# try_two.net
KiCad netlist of a schematic drawn in EAGLE
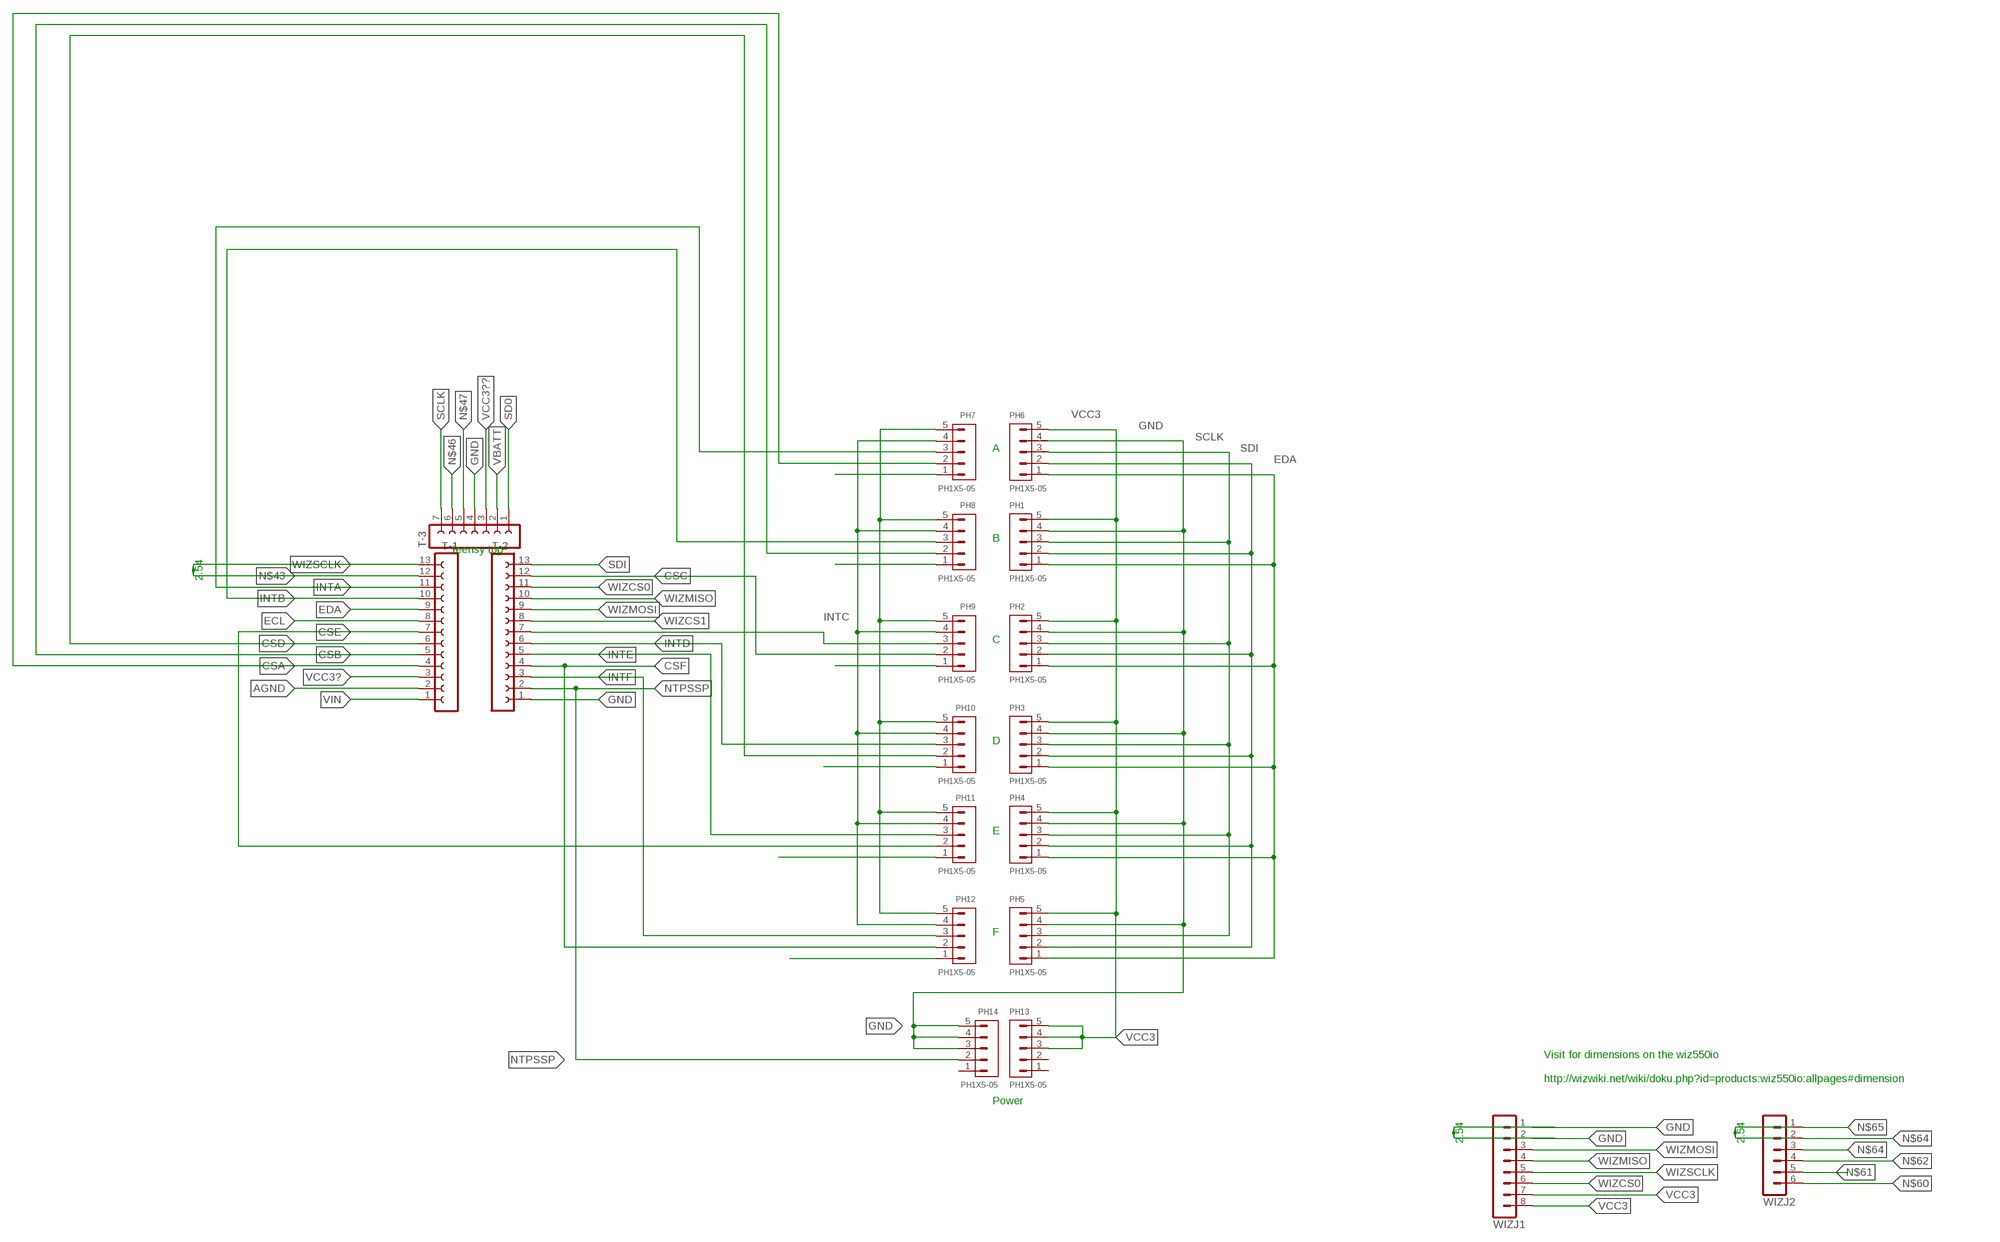
[diagram p0: schematic, sheet 1]

(export (version "E")
  (design (tool "Eeschema 10.0.6"))
  (components
    (comp (ref "PH1")
      (value "PH1X5-05")
      (footprint "eagle-import:PH005-1-5")
      (libsource (lib "eagle-import") (part "PH1X5-05"))
    )
    (comp (ref "PH2")
      (value "PH1X5-05")
      (footprint "eagle-import:PH005-1-5")
      (libsource (lib "eagle-import") (part "PH1X5-05"))
    )
    (comp (ref "PH3")
      (value "PH1X5-05")
      (footprint "eagle-import:PH005-1-5")
      (libsource (lib "eagle-import") (part "PH1X5-05"))
    )
    (comp (ref "PH4")
      (value "PH1X5-05")
      (footprint "eagle-import:PH005-1-5")
      (libsource (lib "eagle-import") (part "PH1X5-05"))
    )
    (comp (ref "PH5")
      (value "PH1X5-05")
      (footprint "eagle-import:PH005-1-5")
      (libsource (lib "eagle-import") (part "PH1X5-05"))
    )
    (comp (ref "PH6")
      (value "PH1X5-05")
      (footprint "eagle-import:PH005-1-5")
      (libsource (lib "eagle-import") (part "PH1X5-05"))
    )
    (comp (ref "PH7")
      (value "PH1X5-05")
      (footprint "eagle-import:PH005-1-5")
      (libsource (lib "eagle-import") (part "PH1X5-05"))
    )
    (comp (ref "PH8")
      (value "PH1X5-05")
      (footprint "eagle-import:PH005-1-5")
      (libsource (lib "eagle-import") (part "PH1X5-05"))
    )
    (comp (ref "PH9")
      (value "PH1X5-05")
      (footprint "eagle-import:PH005-1-5")
      (libsource (lib "eagle-import") (part "PH1X5-05"))
    )
    (comp (ref "PH10")
      (value "PH1X5-05")
      (footprint "eagle-import:PH005-1-5")
      (libsource (lib "eagle-import") (part "PH1X5-05"))
    )
    (comp (ref "PH11")
      (value "PH1X5-05")
      (footprint "eagle-import:PH005-1-5")
      (libsource (lib "eagle-import") (part "PH1X5-05"))
    )
    (comp (ref "PH12")
      (value "PH1X5-05")
      (footprint "eagle-import:PH005-1-5")
      (libsource (lib "eagle-import") (part "PH1X5-05"))
    )
    (comp (ref "PH13")
      (value "PH1X5-05")
      (footprint "eagle-import:PH005-1-5")
      (libsource (lib "eagle-import") (part "PH1X5-05"))
    )
    (comp (ref "PH14")
      (value "PH1X5-05")
      (footprint "eagle-import:PH005-1-5")
      (libsource (lib "eagle-import") (part "PH1X5-05"))
    )
    (comp (ref "T-1")
      (value "FE13-1")
      (footprint "eagle-import:FE13")
      (libsource (lib "eagle-import") (part "FE13-1"))
    )
    (comp (ref "T-2")
      (value "FE13-1")
      (footprint "eagle-import:FE13")
      (libsource (lib "eagle-import") (part "FE13-1"))
    )
    (comp (ref "T-3")
      (value "FE07-1")
      (footprint "eagle-import:FE07")
      (libsource (lib "eagle-import") (part "FE07-1"))
    )
    (comp (ref "WIZJ1")
      (value "MA08-1")
      (footprint "eagle-import:MA08-1")
      (libsource (lib "eagle-import") (part "MA08-1"))
    )
    (comp (ref "WIZJ2")
      (value "MA06-1")
      (footprint "eagle-import:MA06-1")
      (libsource (lib "eagle-import") (part "MA06-1"))
    )
  )
  (nets
    (net (code "1") (name "/INTC") (class "Default")
      (node (ref "PH9") (pin "3") (pinfunction "3_3") (pintype "bidirectional"))
      (node (ref "T-2") (pin "7") (pinfunction "7_7") (pintype "passive"))
    )
    (net (code "2") (name "AGND") (class "Default")
      (node (ref "T-1") (pin "2") (pinfunction "2_2") (pintype "passive"))
    )
    (net (code "3") (name "CSA") (class "Default")
      (node (ref "PH7") (pin "2") (pinfunction "2_2") (pintype "bidirectional"))
      (node (ref "T-1") (pin "4") (pinfunction "4_4") (pintype "passive"))
    )
    (net (code "4") (name "CSB") (class "Default")
      (node (ref "PH8") (pin "2") (pinfunction "2_2") (pintype "bidirectional"))
      (node (ref "T-1") (pin "5") (pinfunction "5_5") (pintype "passive"))
    )
    (net (code "5") (name "CSC") (class "Default")
      (node (ref "PH9") (pin "2") (pinfunction "2_2") (pintype "bidirectional"))
      (node (ref "T-2") (pin "12") (pinfunction "12_12") (pintype "passive"))
    )
    (net (code "6") (name "CSD") (class "Default")
      (node (ref "PH10") (pin "2") (pinfunction "2_2") (pintype "bidirectional"))
      (node (ref "T-1") (pin "6") (pinfunction "6_6") (pintype "passive"))
    )
    (net (code "7") (name "CSE") (class "Default")
      (node (ref "PH11") (pin "2") (pinfunction "2_2") (pintype "bidirectional"))
      (node (ref "T-1") (pin "7") (pinfunction "7_7") (pintype "passive"))
    )
    (net (code "8") (name "CSF") (class "Default")
      (node (ref "PH12") (pin "2") (pinfunction "2_2") (pintype "bidirectional"))
      (node (ref "T-2") (pin "4") (pinfunction "4_4") (pintype "passive"))
    )
    (net (code "9") (name "ECL") (class "Default")
      (node (ref "PH10") (pin "5") (pinfunction "5_5") (pintype "bidirectional"))
      (node (ref "PH11") (pin "5") (pinfunction "5_5") (pintype "bidirectional"))
      (node (ref "PH12") (pin "5") (pinfunction "5_5") (pintype "bidirectional"))
      (node (ref "PH7") (pin "5") (pinfunction "5_5") (pintype "bidirectional"))
      (node (ref "PH8") (pin "5") (pinfunction "5_5") (pintype "bidirectional"))
      (node (ref "PH9") (pin "5") (pinfunction "5_5") (pintype "bidirectional"))
      (node (ref "T-1") (pin "8") (pinfunction "8_8") (pintype "passive"))
    )
    (net (code "10") (name "EDA") (class "Default")
      (node (ref "PH1") (pin "1") (pinfunction "1_1") (pintype "bidirectional"))
      (node (ref "PH2") (pin "1") (pinfunction "1_1") (pintype "bidirectional"))
      (node (ref "PH3") (pin "1") (pinfunction "1_1") (pintype "bidirectional"))
      (node (ref "PH4") (pin "1") (pinfunction "1_1") (pintype "bidirectional"))
      (node (ref "PH5") (pin "1") (pinfunction "1_1") (pintype "bidirectional"))
      (node (ref "PH6") (pin "1") (pinfunction "1_1") (pintype "bidirectional"))
      (node (ref "T-1") (pin "9") (pinfunction "9_9") (pintype "passive"))
    )
    (net (code "11") (name "GND") (class "Default")
      (node (ref "PH1") (pin "4") (pinfunction "4_4") (pintype "bidirectional"))
      (node (ref "PH14") (pin "3") (pinfunction "3_3") (pintype "bidirectional"))
      (node (ref "PH14") (pin "4") (pinfunction "4_4") (pintype "bidirectional"))
      (node (ref "PH14") (pin "5") (pinfunction "5_5") (pintype "bidirectional"))
      (node (ref "PH2") (pin "4") (pinfunction "4_4") (pintype "bidirectional"))
      (node (ref "PH3") (pin "4") (pinfunction "4_4") (pintype "bidirectional"))
      (node (ref "PH4") (pin "4") (pinfunction "4_4") (pintype "bidirectional"))
      (node (ref "PH5") (pin "4") (pinfunction "4_4") (pintype "bidirectional"))
      (node (ref "PH6") (pin "4") (pinfunction "4_4") (pintype "bidirectional"))
      (node (ref "T-2") (pin "1") (pinfunction "1_1") (pintype "passive"))
      (node (ref "T-3") (pin "4") (pinfunction "4_4") (pintype "passive"))
      (node (ref "WIZJ1") (pin "1") (pinfunction "1_1") (pintype "passive"))
      (node (ref "WIZJ1") (pin "2") (pinfunction "2_2") (pintype "passive"))
    )
    (net (code "12") (name "INTA") (class "Default")
      (node (ref "PH7") (pin "3") (pinfunction "3_3") (pintype "bidirectional"))
      (node (ref "T-1") (pin "11") (pinfunction "11_11") (pintype "passive"))
    )
    (net (code "13") (name "INTB") (class "Default")
      (node (ref "PH8") (pin "3") (pinfunction "3_3") (pintype "bidirectional"))
      (node (ref "T-1") (pin "10") (pinfunction "10_10") (pintype "passive"))
    )
    (net (code "14") (name "INTD") (class "Default")
      (node (ref "PH10") (pin "3") (pinfunction "3_3") (pintype "bidirectional"))
      (node (ref "T-2") (pin "6") (pinfunction "6_6") (pintype "passive"))
    )
    (net (code "15") (name "INTE") (class "Default")
      (node (ref "PH11") (pin "3") (pinfunction "3_3") (pintype "bidirectional"))
      (node (ref "T-2") (pin "5") (pinfunction "5_5") (pintype "passive"))
    )
    (net (code "16") (name "INTF") (class "Default")
      (node (ref "PH12") (pin "3") (pinfunction "3_3") (pintype "bidirectional"))
      (node (ref "T-2") (pin "3") (pinfunction "3_3") (pintype "passive"))
    )
    (net (code "17") (name "N$43") (class "Default")
      (node (ref "T-1") (pin "12") (pinfunction "12_12") (pintype "passive"))
    )
    (net (code "18") (name "N$46") (class "Default")
      (node (ref "T-3") (pin "6") (pinfunction "6_6") (pintype "passive"))
    )
    (net (code "19") (name "N$47") (class "Default")
      (node (ref "T-3") (pin "5") (pinfunction "5_5") (pintype "passive"))
    )
    (net (code "20") (name "N$60") (class "Default")
      (node (ref "WIZJ2") (pin "6") (pinfunction "6_6") (pintype "passive"))
    )
    (net (code "21") (name "N$61") (class "Default")
      (node (ref "WIZJ2") (pin "5") (pinfunction "5_5") (pintype "passive"))
    )
    (net (code "22") (name "N$62") (class "Default")
      (node (ref "WIZJ2") (pin "4") (pinfunction "4_4") (pintype "passive"))
    )
    (net (code "23") (name "N$64") (class "Default")
      (node (ref "WIZJ2") (pin "2") (pinfunction "2_2") (pintype "passive"))
    )
    (net (code "24") (name "N$65") (class "Default")
      (node (ref "WIZJ2") (pin "1") (pinfunction "1_1") (pintype "passive"))
    )
    (net (code "25") (name "NTPSSP") (class "Default")
      (node (ref "PH14") (pin "2") (pinfunction "2_2") (pintype "bidirectional"))
      (node (ref "T-2") (pin "2") (pinfunction "2_2") (pintype "passive"))
    )
    (net (code "26") (name "SCLK") (class "Default")
      (node (ref "PH1") (pin "3") (pinfunction "3_3") (pintype "bidirectional"))
      (node (ref "PH2") (pin "3") (pinfunction "3_3") (pintype "bidirectional"))
      (node (ref "PH3") (pin "3") (pinfunction "3_3") (pintype "bidirectional"))
      (node (ref "PH4") (pin "3") (pinfunction "3_3") (pintype "bidirectional"))
      (node (ref "PH5") (pin "3") (pinfunction "3_3") (pintype "bidirectional"))
      (node (ref "PH6") (pin "3") (pinfunction "3_3") (pintype "bidirectional"))
      (node (ref "T-3") (pin "7") (pinfunction "7_7") (pintype "passive"))
    )
    (net (code "27") (name "SD0") (class "Default")
      (node (ref "PH10") (pin "4") (pinfunction "4_4") (pintype "bidirectional"))
      (node (ref "PH11") (pin "4") (pinfunction "4_4") (pintype "bidirectional"))
      (node (ref "PH12") (pin "4") (pinfunction "4_4") (pintype "bidirectional"))
      (node (ref "PH7") (pin "4") (pinfunction "4_4") (pintype "bidirectional"))
      (node (ref "PH8") (pin "4") (pinfunction "4_4") (pintype "bidirectional"))
      (node (ref "PH9") (pin "4") (pinfunction "4_4") (pintype "bidirectional"))
      (node (ref "T-3") (pin "1") (pinfunction "1_1") (pintype "passive"))
    )
    (net (code "28") (name "SDI") (class "Default")
      (node (ref "PH1") (pin "2") (pinfunction "2_2") (pintype "bidirectional"))
      (node (ref "PH2") (pin "2") (pinfunction "2_2") (pintype "bidirectional"))
      (node (ref "PH3") (pin "2") (pinfunction "2_2") (pintype "bidirectional"))
      (node (ref "PH4") (pin "2") (pinfunction "2_2") (pintype "bidirectional"))
      (node (ref "PH5") (pin "2") (pinfunction "2_2") (pintype "bidirectional"))
      (node (ref "PH6") (pin "2") (pinfunction "2_2") (pintype "bidirectional"))
      (node (ref "T-2") (pin "13") (pinfunction "13_13") (pintype "passive"))
    )
    (net (code "29") (name "VBATT") (class "Default")
      (node (ref "T-3") (pin "2") (pinfunction "2_2") (pintype "passive"))
    )
    (net (code "30") (name "VCC3") (class "Default")
      (node (ref "PH1") (pin "5") (pinfunction "5_5") (pintype "bidirectional"))
      (node (ref "PH13") (pin "3") (pinfunction "3_3") (pintype "bidirectional"))
      (node (ref "PH13") (pin "4") (pinfunction "4_4") (pintype "bidirectional"))
      (node (ref "PH13") (pin "5") (pinfunction "5_5") (pintype "bidirectional"))
      (node (ref "PH2") (pin "5") (pinfunction "5_5") (pintype "bidirectional"))
      (node (ref "PH3") (pin "5") (pinfunction "5_5") (pintype "bidirectional"))
      (node (ref "PH4") (pin "5") (pinfunction "5_5") (pintype "bidirectional"))
      (node (ref "PH5") (pin "5") (pinfunction "5_5") (pintype "bidirectional"))
      (node (ref "PH6") (pin "5") (pinfunction "5_5") (pintype "bidirectional"))
      (node (ref "WIZJ1") (pin "7") (pinfunction "7_7") (pintype "passive"))
      (node (ref "WIZJ1") (pin "8") (pinfunction "8_8") (pintype "passive"))
    )
    (net (code "31") (name "VCC3?") (class "Default")
      (node (ref "T-1") (pin "3") (pinfunction "3_3") (pintype "passive"))
    )
    (net (code "32") (name "VCC3??") (class "Default")
      (node (ref "T-3") (pin "3") (pinfunction "3_3") (pintype "passive"))
    )
    (net (code "33") (name "VIN") (class "Default")
      (node (ref "T-1") (pin "1") (pinfunction "1_1") (pintype "passive"))
    )
    (net (code "34") (name "WIZCS0") (class "Default")
      (node (ref "T-2") (pin "11") (pinfunction "11_11") (pintype "passive"))
      (node (ref "WIZJ1") (pin "6") (pinfunction "6_6") (pintype "passive"))
    )
    (net (code "35") (name "WIZCS1") (class "Default")
      (node (ref "T-2") (pin "8") (pinfunction "8_8") (pintype "passive"))
    )
    (net (code "36") (name "WIZMISO") (class "Default")
      (node (ref "T-2") (pin "10") (pinfunction "10_10") (pintype "passive"))
      (node (ref "WIZJ1") (pin "4") (pinfunction "4_4") (pintype "passive"))
    )
    (net (code "37") (name "WIZMOSI") (class "Default")
      (node (ref "T-2") (pin "9") (pinfunction "9_9") (pintype "passive"))
      (node (ref "WIZJ1") (pin "3") (pinfunction "3_3") (pintype "passive"))
    )
    (net (code "38") (name "WIZSCLK") (class "Default")
      (node (ref "T-1") (pin "13") (pinfunction "13_13") (pintype "passive"))
      (node (ref "WIZJ1") (pin "5") (pinfunction "5_5") (pintype "passive"))
    )
    (net (code "39") (name "unconnected-(PH7-Pad1)") (class "Default")
      (node (ref "PH7") (pin "1") (pinfunction "1_1") (pintype "bidirectional"))
    )
    (net (code "40") (name "unconnected-(PH8-Pad1)") (class "Default")
      (node (ref "PH8") (pin "1") (pinfunction "1_1") (pintype "bidirectional"))
    )
    (net (code "41") (name "unconnected-(PH9-Pad1)") (class "Default")
      (node (ref "PH9") (pin "1") (pinfunction "1_1") (pintype "bidirectional"))
    )
    (net (code "42") (name "unconnected-(PH10-Pad1)") (class "Default")
      (node (ref "PH10") (pin "1") (pinfunction "1_1") (pintype "bidirectional"))
    )
    (net (code "43") (name "unconnected-(PH11-Pad1)") (class "Default")
      (node (ref "PH11") (pin "1") (pinfunction "1_1") (pintype "bidirectional"))
    )
    (net (code "44") (name "unconnected-(PH12-Pad1)") (class "Default")
      (node (ref "PH12") (pin "1") (pinfunction "1_1") (pintype "bidirectional"))
    )
    (net (code "45") (name "unconnected-(PH13-Pad1)") (class "Default")
      (node (ref "PH13") (pin "1") (pinfunction "1_1") (pintype "bidirectional"))
    )
    (net (code "46") (name "unconnected-(PH13-Pad2)") (class "Default")
      (node (ref "PH13") (pin "2") (pinfunction "2_2") (pintype "bidirectional"))
    )
    (net (code "47") (name "unconnected-(PH14-Pad1)") (class "Default")
      (node (ref "PH14") (pin "1") (pinfunction "1_1") (pintype "bidirectional"))
    )
    (net (code "48") (name "unconnected-(WIZJ2-Pad3)") (class "Default")
      (node (ref "WIZJ2") (pin "3") (pinfunction "3_3") (pintype "passive"))
    )
  )
)
